# OSWDKPCB.net
KiCad netlist of a schematic drawn in EAGLE
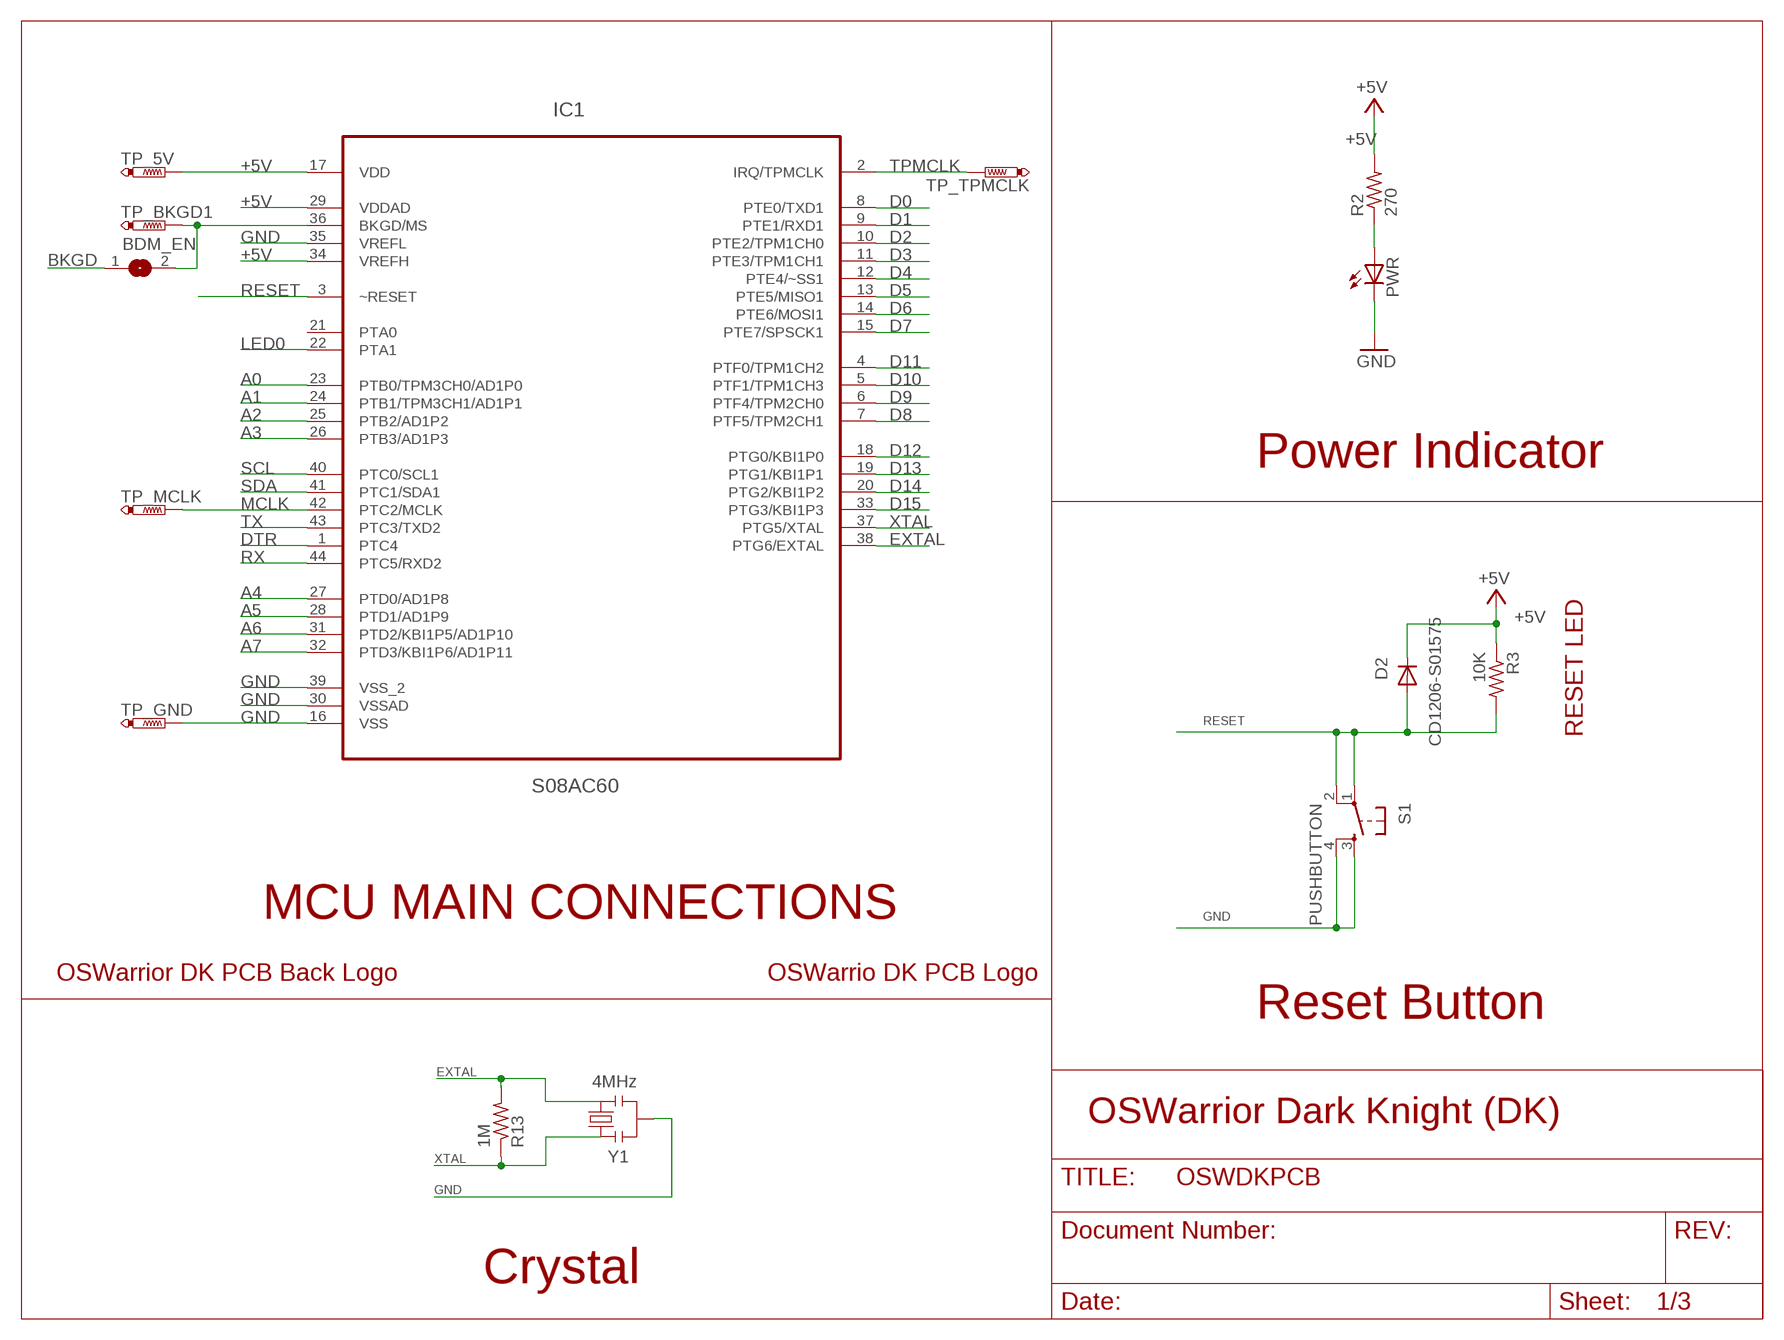
[diagram p0: schematic, sheet 1]
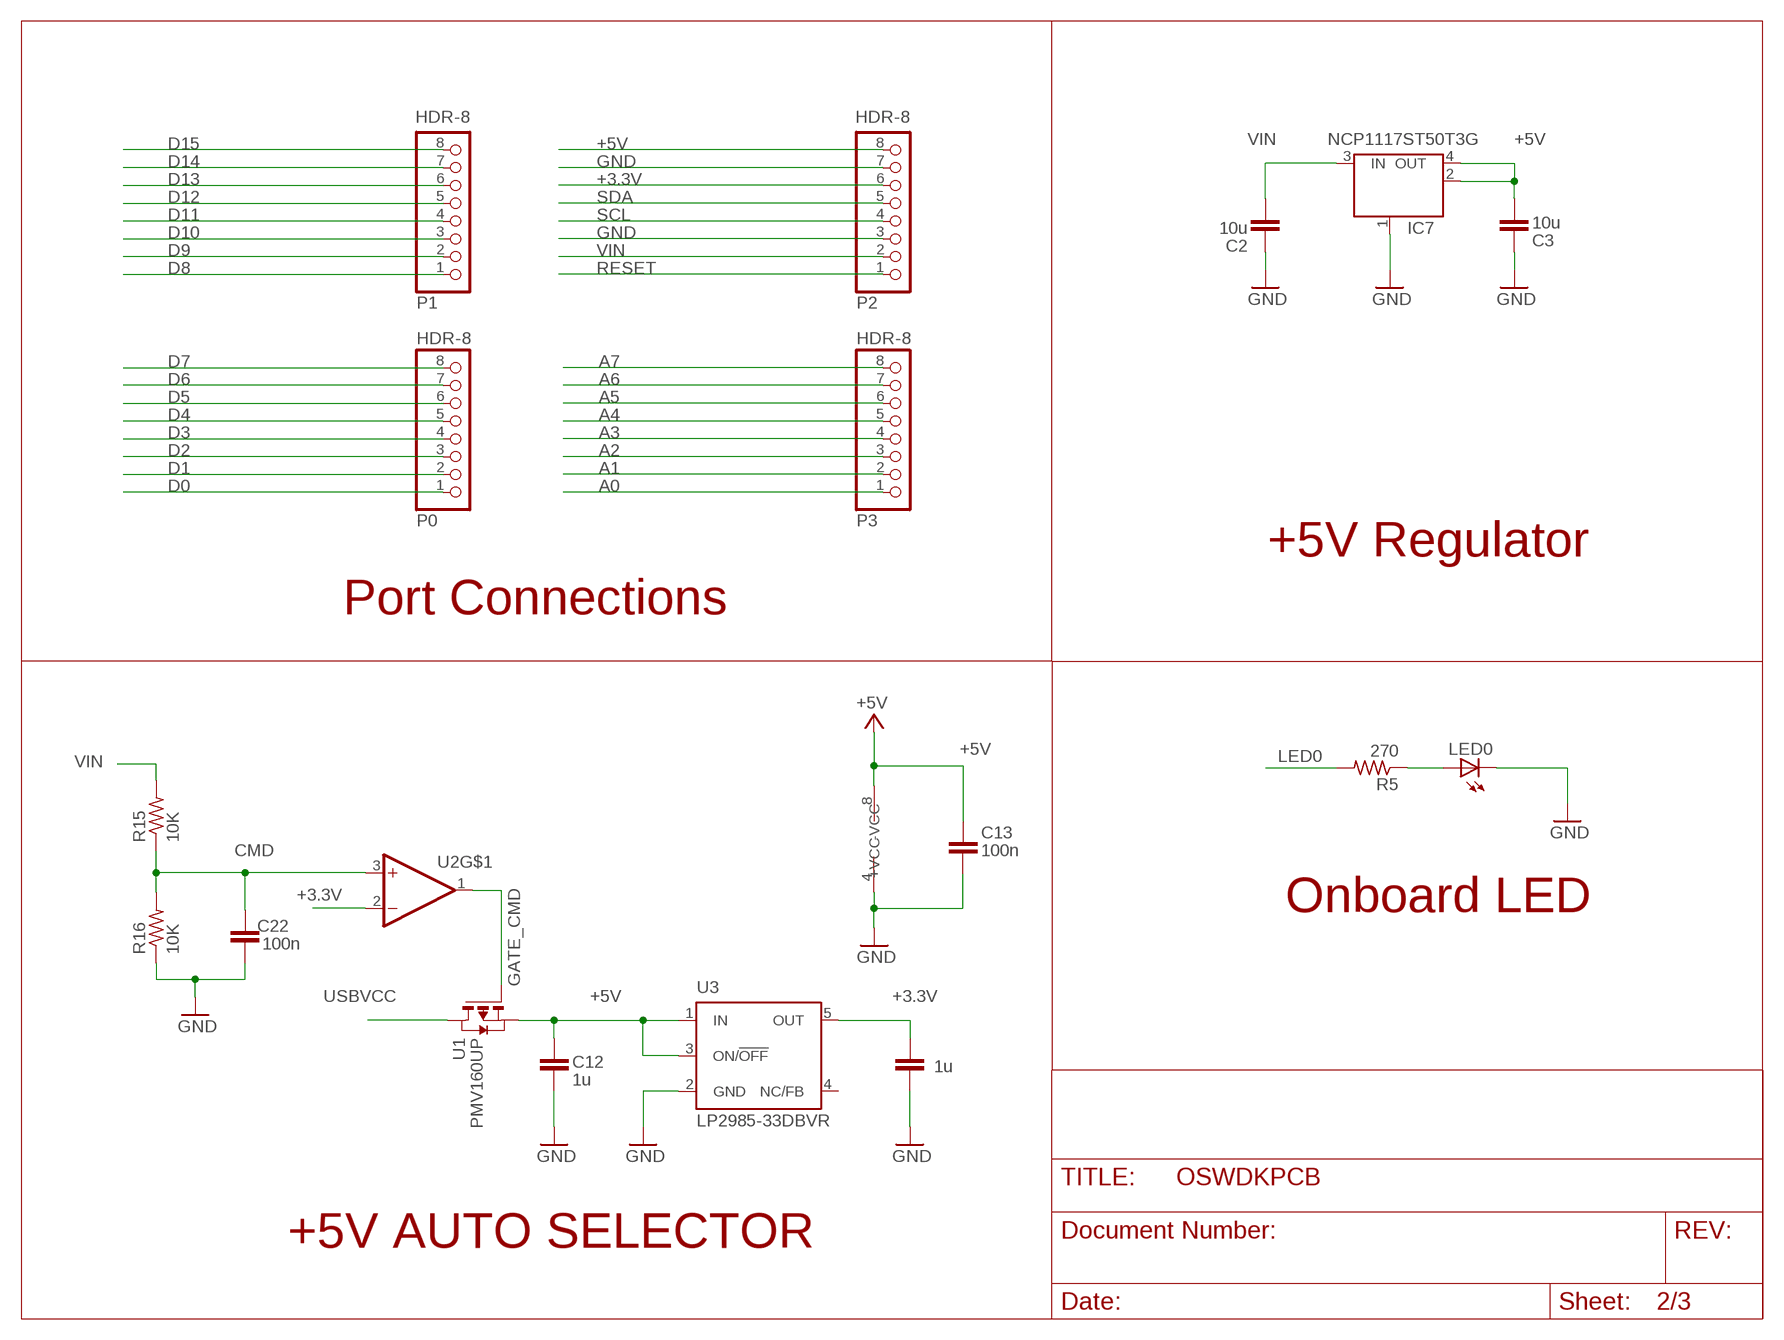
[diagram p1: schematic, sheet 2]
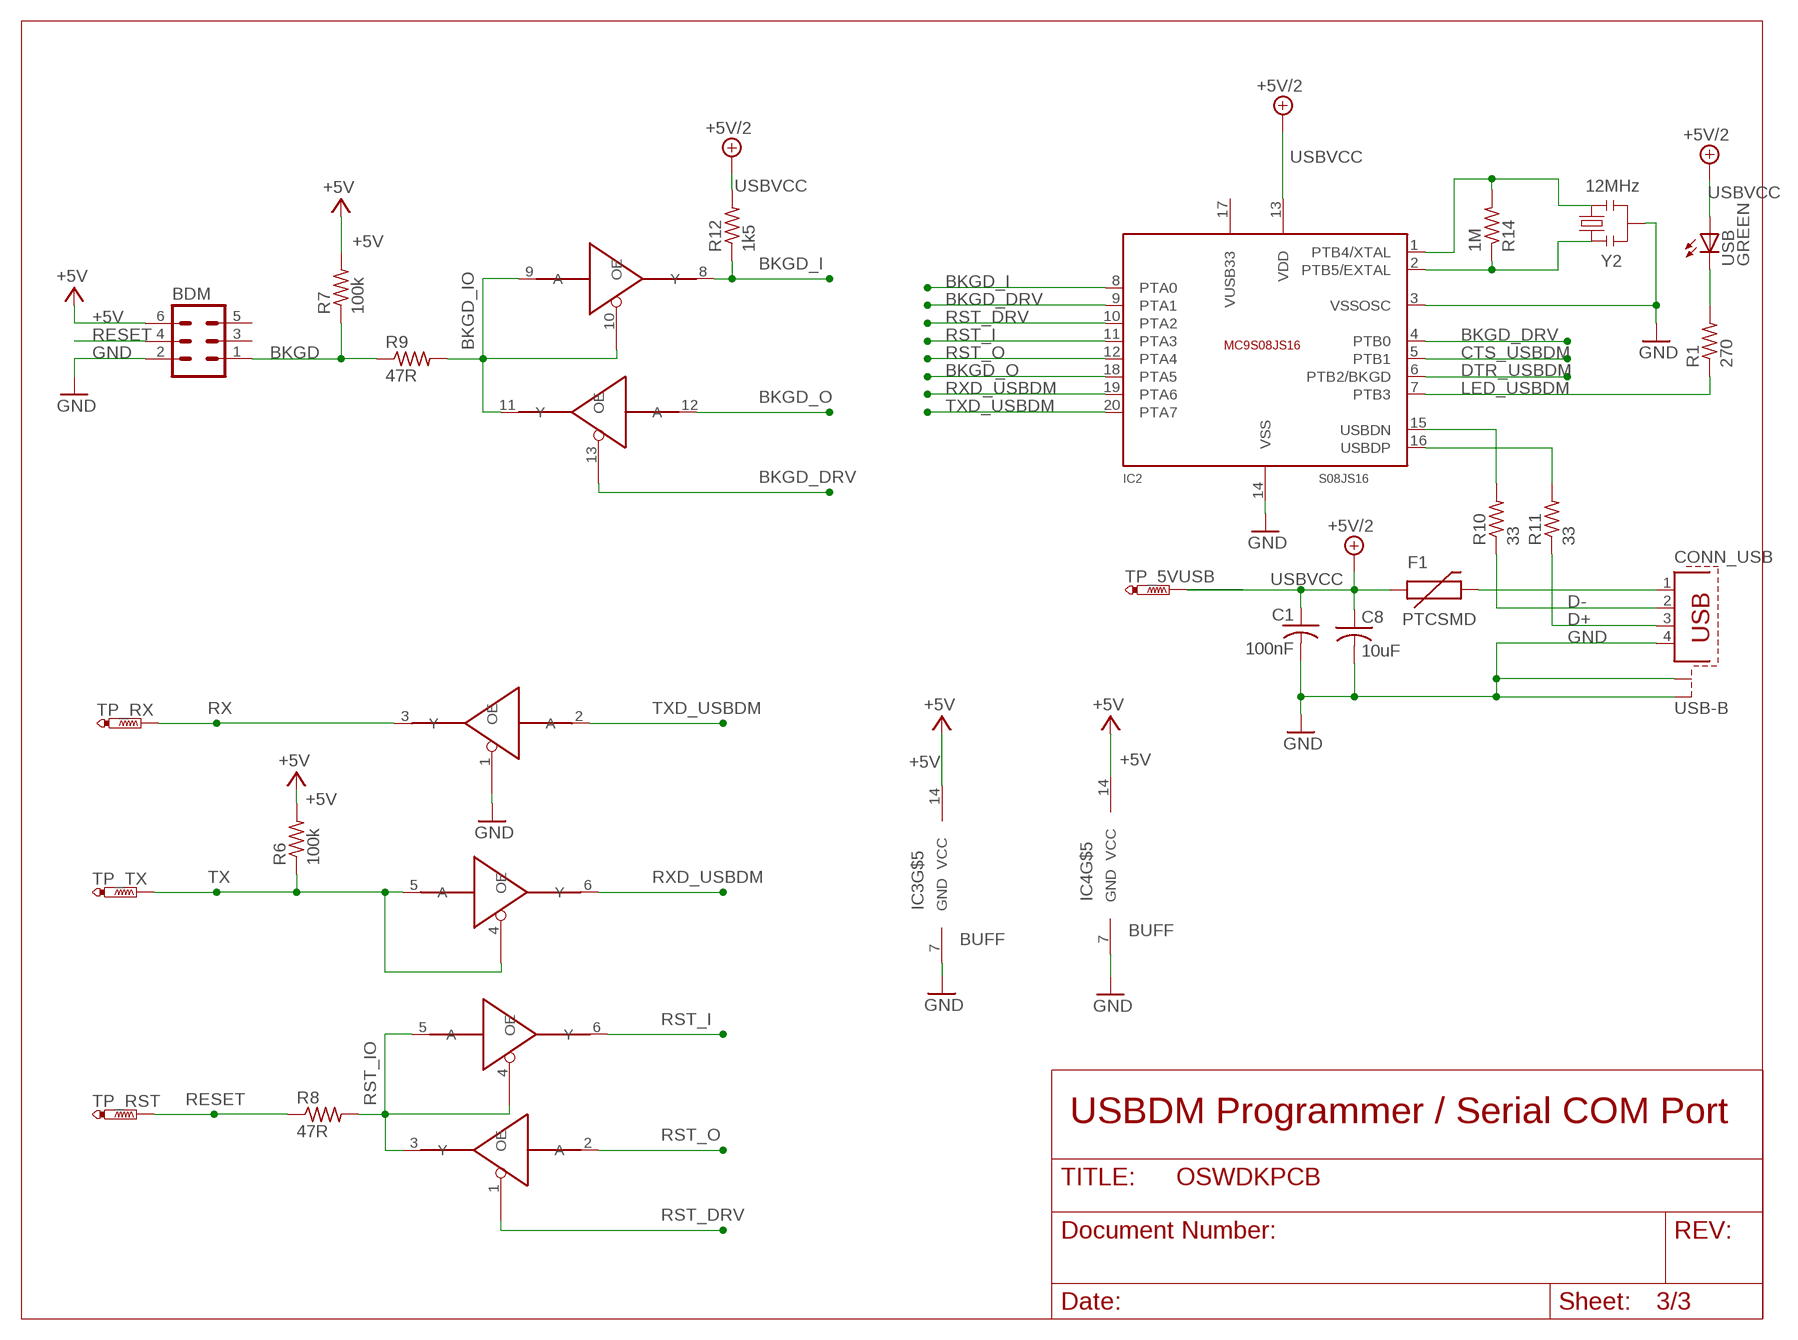
[diagram p2: schematic, sheet 3]

(export (version "E")
  (design (tool "Eeschema 10.0.6"))
  (components
    (comp (ref "BDM_EN")
      (value "SJ")
      (footprint "eagle-import:SJ")
      (libsource (lib "eagle-import") (part "SJ"))
    )
    (comp (ref "D2")
      (value "CD1206-S01575")
      (footprint "eagle-import:SOD123")
      (libsource (lib "eagle-import") (part "DIODE-SOD123"))
    )
    (comp (ref "IC1")
      (value "S08AC60")
      (footprint "eagle-import:LQFP-44")
      (libsource (lib "eagle-import") (part "MC9S08AC48CFGE_LQFP-44"))
    )
    (comp (ref "PWR")
      (value "LEDCHIPLED_0805")
      (footprint "eagle-import:CHIPLED_0805")
      (libsource (lib "eagle-import") (part "LEDCHIPLED_0805"))
    )
    (comp (ref "R2")
      (value "270")
      (footprint "eagle-import:M0805")
      (libsource (lib "eagle-import") (part "R-US_M0805"))
    )
    (comp (ref "R3")
      (value "10K")
      (footprint "eagle-import:M0805")
      (libsource (lib "eagle-import") (part "R-US_M0805"))
    )
    (comp (ref "R13")
      (value "1M")
      (footprint "eagle-import:M0805")
      (libsource (lib "eagle-import") (part "R-US_M0805"))
    )
    (comp (ref "S1")
      (value "PUSHBUTTON")
      (footprint "eagle-import:TACTILE-PTH")
      (libsource (lib "eagle-import") (part "TAC_SWITCHPTH"))
    )
    (comp (ref "TP_5V")
      (value "PTR1B1,27")
      (footprint "eagle-import:B1,27")
      (libsource (lib "eagle-import") (part "PTR1B1,27"))
    )
    (comp (ref "TP_BKGD1")
      (value "PTR1B1,27")
      (footprint "eagle-import:B1,27")
      (libsource (lib "eagle-import") (part "PTR1B1,27"))
    )
    (comp (ref "TP_GND")
      (value "PTR1B1,27")
      (footprint "eagle-import:B1,27")
      (libsource (lib "eagle-import") (part "PTR1B1,27"))
    )
    (comp (ref "TP_MCLK")
      (value "PTR1B1,27")
      (footprint "eagle-import:B1,27")
      (libsource (lib "eagle-import") (part "PTR1B1,27"))
    )
    (comp (ref "TP_TPMCLK")
      (value "PTR1B1,27")
      (footprint "eagle-import:B1,27")
      (libsource (lib "eagle-import") (part "PTR1B1,27"))
    )
    (comp (ref "U$1")
      (value "OSWDK_LOGO")
      (footprint "eagle-import:OSWDK_LOGO")
      (libsource (lib "eagle-import") (part "OSWDK_LOGO"))
    )
    (comp (ref "U$2")
      (value "OSWDK_BACK_LOGO")
      (footprint "eagle-import:OSWDK_BACK_LOGO")
      (libsource (lib "eagle-import") (part "OSWDK_BACK_LOGO"))
    )
    (comp (ref "Y1")
      (value "4MHz")
      (footprint "eagle-import:RESONATOR-SMD")
      (libsource (lib "eagle-import") (part "RESONATORSMD"))
    )
    (comp (ref "BDM")
      (value "MA03-2")
      (footprint "eagle-import:MA03-2")
      (libsource (lib "eagle-import") (part "MA03-2"))
    )
    (comp (ref "C1")
      (value "100nF")
      (footprint "eagle-import:C0805")
      (libsource (lib "eagle-import") (part "C-USC0805"))
    )
    (comp (ref "C8")
      (value "10uF")
      (footprint "eagle-import:C0805")
      (libsource (lib "eagle-import") (part "C-USC0805"))
    )
    (comp (ref "CONN_USB")
      (value "USB-B")
      (footprint "eagle-import:PN61729-S")
      (libsource (lib "eagle-import") (part "PN61729-S"))
    )
    (comp (ref "F1")
      (value "PTCSMD")
      (footprint "eagle-import:PTC-1206")
      (libsource (lib "eagle-import") (part "PTCSMD"))
    )
    (comp (ref "IC2")
      (value "S08JS16")
      (footprint "eagle-import:SOIC-20")
      (libsource (lib "eagle-import") (part "MC9S08JS16CWJ_SOIC-20"))
    )
    (comp (ref "IC3")
      (value "BUFF")
      (footprint "eagle-import:TSSOP-14")
      (libsource (lib "eagle-import") (part "SN74LV125APW_TSSOP-14"))
    )
    (comp (ref "IC4")
      (value "BUFF")
      (footprint "eagle-import:TSSOP-14")
      (libsource (lib "eagle-import") (part "SN74LV125APW_TSSOP-14"))
    )
    (comp (ref "R1")
      (value "270")
      (footprint "eagle-import:M0805")
      (libsource (lib "eagle-import") (part "R-US_M0805"))
    )
    (comp (ref "R6")
      (value "100k")
      (footprint "eagle-import:M0805")
      (libsource (lib "eagle-import") (part "R-US_M0805"))
    )
    (comp (ref "R7")
      (value "100k")
      (footprint "eagle-import:M0805")
      (libsource (lib "eagle-import") (part "R-US_M0805"))
    )
    (comp (ref "R8")
      (value "47R")
      (footprint "eagle-import:M0805")
      (libsource (lib "eagle-import") (part "R-US_M0805"))
    )
    (comp (ref "R9")
      (value "47R")
      (footprint "eagle-import:M0805")
      (libsource (lib "eagle-import") (part "R-US_M0805"))
    )
    (comp (ref "R10")
      (value "33")
      (footprint "eagle-import:M0805")
      (libsource (lib "eagle-import") (part "R-US_M0805"))
    )
    (comp (ref "R11")
      (value "33")
      (footprint "eagle-import:M0805")
      (libsource (lib "eagle-import") (part "R-US_M0805"))
    )
    (comp (ref "R12")
      (value "1k5")
      (footprint "eagle-import:M0805")
      (libsource (lib "eagle-import") (part "R-US_M0805"))
    )
    (comp (ref "R14")
      (value "1M")
      (footprint "eagle-import:M0805")
      (libsource (lib "eagle-import") (part "R-US_M0805"))
    )
    (comp (ref "TP_5VUSB")
      (value "PTR1B1,27")
      (footprint "eagle-import:B1,27")
      (libsource (lib "eagle-import") (part "PTR1B1,27"))
    )
    (comp (ref "TP_RST")
      (value "PTR1B1,27")
      (footprint "eagle-import:B1,27")
      (libsource (lib "eagle-import") (part "PTR1B1,27"))
    )
    (comp (ref "TP_RX")
      (value "PTR1B1,27")
      (footprint "eagle-import:B1,27")
      (libsource (lib "eagle-import") (part "PTR1B1,27"))
    )
    (comp (ref "TP_TX")
      (value "PTR1B1,27")
      (footprint "eagle-import:B1,27")
      (libsource (lib "eagle-import") (part "PTR1B1,27"))
    )
    (comp (ref "USB")
      (value "GREEN")
      (footprint "eagle-import:CHIPLED_0805")
      (libsource (lib "eagle-import") (part "LEDCHIPLED_0805"))
    )
    (comp (ref "Y2")
      (value "12MHz")
      (footprint "eagle-import:RESONATOR-SMD")
      (libsource (lib "eagle-import") (part "RESONATORSMD"))
    )
    (comp (ref "C2")
      (value "10u")
      (footprint "eagle-import:C0805")
      (libsource (lib "eagle-import") (part "C-EUC0805"))
    )
    (comp (ref "C3")
      (value "10u")
      (footprint "eagle-import:C0805")
      (libsource (lib "eagle-import") (part "C-EUC0805"))
    )
    (comp (ref "C12")
      (value "1u")
      (footprint "eagle-import:C0805")
      (libsource (lib "eagle-import") (part "C-EUC0805"))
    )
    (comp (ref "C13")
      (value "100n")
      (footprint "eagle-import:C0805")
      (libsource (lib "eagle-import") (part "C-EUC0805"))
    )
    (comp (ref "C14")
      (value "1u")
      (footprint "eagle-import:C0805")
      (libsource (lib "eagle-import") (part "C-EUC0805"))
    )
    (comp (ref "C22")
      (value "100n")
      (footprint "eagle-import:C0805")
      (libsource (lib "eagle-import") (part "C-EUC0805"))
    )
    (comp (ref "IC7")
      (value "NCP1117ST50T3G")
      (footprint "eagle-import:SOT223")
      (libsource (lib "eagle-import") (part "MC33269ST-3.3T3"))
    )
    (comp (ref "LED0")
      (value "LEDCHIPLED_0805")
      (footprint "eagle-import:CHIPLED_0805")
      (libsource (lib "eagle-import") (part "LEDCHIPLED_0805"))
    )
    (comp (ref "P0")
      (value "HDR-8")
      (footprint "eagle-import:1X08")
      (libsource (lib "eagle-import") (part "PINHD-1X8"))
    )
    (comp (ref "P1")
      (value "HDR-8")
      (footprint "eagle-import:1X08")
      (libsource (lib "eagle-import") (part "PINHD-1X8"))
    )
    (comp (ref "P2")
      (value "HDR-8")
      (footprint "eagle-import:1X08")
      (libsource (lib "eagle-import") (part "PINHD-1X8"))
    )
    (comp (ref "P3")
      (value "HDR-8")
      (footprint "eagle-import:1X08")
      (libsource (lib "eagle-import") (part "PINHD-1X8"))
    )
    (comp (ref "R5")
      (value "270")
      (footprint "eagle-import:M0805")
      (libsource (lib "eagle-import") (part "R-US_M0805"))
    )
    (comp (ref "R15")
      (value "10K")
      (footprint "eagle-import:M0805")
      (libsource (lib "eagle-import") (part "R-US_M0805"))
    )
    (comp (ref "R16")
      (value "10K")
      (footprint "eagle-import:M0805")
      (libsource (lib "eagle-import") (part "R-US_M0805"))
    )
    (comp (ref "U1")
      (value "PMV160UP")
      (footprint "eagle-import:SOT-23")
      (libsource (lib "eagle-import") (part "PMV160UP"))
    )
    (comp (ref "U2")
      (value "RC4558")
      (footprint "eagle-import:SOIC-8")
      (libsource (lib "eagle-import") (part "RC4558"))
    )
    (comp (ref "U3")
      (value "LP2985-33DBVR")
      (footprint "eagle-import:SOT23-DBV")
      (libsource (lib "eagle-import") (part "LP2985-XXDBVR33"))
    )
  )
  (nets
    (net (code "1") (name "+3.3V") (class "Default")
      (node (ref "C14") (pin "2") (pinfunction "2_2") (pintype "passive"))
      (node (ref "P2") (pin "6") (pinfunction "6_6") (pintype "passive"))
      (node (ref "U2") (pin "2") (pinfunction "-IN1_2") (pintype "input"))
      (node (ref "U3") (pin "5") (pinfunction "OUT_5") (pintype "passive"))
    )
    (net (code "2") (name "+5V") (class "Default")
      (node (ref "BDM") (pin "6") (pinfunction "6_6") (pintype "passive"))
      (node (ref "C12") (pin "2") (pinfunction "2_2") (pintype "passive"))
      (node (ref "C13") (pin "1") (pinfunction "1_1") (pintype "passive"))
      (node (ref "C3") (pin "1") (pinfunction "1_1") (pintype "passive"))
      (node (ref "D2") (pin "C") (pinfunction "C_C") (pintype "passive"))
      (node (ref "IC1") (pin "17") (pinfunction "VDD_17") (pintype "power_in"))
      (node (ref "IC1") (pin "29") (pinfunction "VDDAD_29") (pintype "power_in"))
      (node (ref "IC1") (pin "34") (pinfunction "VREFH_34") (pintype "input"))
      (node (ref "IC3") (pin "14") (pinfunction "VCC_14") (pintype "power_in"))
      (node (ref "IC4") (pin "14") (pinfunction "VCC_14") (pintype "power_in"))
      (node (ref "IC7") (pin "2") (pinfunction "OUT_2") (pintype "passive"))
      (node (ref "IC7") (pin "4") (pinfunction "OUT_4") (pintype "passive"))
      (node (ref "P2") (pin "8") (pinfunction "8_8") (pintype "passive"))
      (node (ref "R2") (pin "2") (pinfunction "2_2") (pintype "passive"))
      (node (ref "R3") (pin "1") (pinfunction "1_1") (pintype "passive"))
      (node (ref "R6") (pin "2") (pinfunction "2_2") (pintype "passive"))
      (node (ref "R7") (pin "2") (pinfunction "2_2") (pintype "passive"))
      (node (ref "TP_5V") (pin "TP") (pinfunction "TP_TP") (pintype "input"))
      (node (ref "U1") (pin "2") (pinfunction "S_2") (pintype "passive"))
      (node (ref "U2") (pin "8") (pinfunction "+VCC_8") (pintype "power_in"))
      (node (ref "U3") (pin "1") (pinfunction "IN_1") (pintype "input"))
      (node (ref "U3") (pin "3") (pinfunction "ON/~{OFF}_3") (pintype "input"))
    )
    (net (code "3") (name "A0") (class "Default")
      (node (ref "IC1") (pin "23") (pinfunction "PTB0/TPM3CH0/AD1P0_23") (pintype "bidirectional"))
      (node (ref "P3") (pin "1") (pinfunction "1_1") (pintype "passive"))
    )
    (net (code "4") (name "A1") (class "Default")
      (node (ref "IC1") (pin "24") (pinfunction "PTB1/TPM3CH1/AD1P1_24") (pintype "bidirectional"))
      (node (ref "P3") (pin "2") (pinfunction "2_2") (pintype "passive"))
    )
    (net (code "5") (name "A2") (class "Default")
      (node (ref "IC1") (pin "25") (pinfunction "PTB2/AD1P2_25") (pintype "bidirectional"))
      (node (ref "P3") (pin "3") (pinfunction "3_3") (pintype "passive"))
    )
    (net (code "6") (name "A3") (class "Default")
      (node (ref "IC1") (pin "26") (pinfunction "PTB3/AD1P3_26") (pintype "bidirectional"))
      (node (ref "P3") (pin "4") (pinfunction "4_4") (pintype "passive"))
    )
    (net (code "7") (name "A4") (class "Default")
      (node (ref "IC1") (pin "27") (pinfunction "PTD0/AD1P8_27") (pintype "bidirectional"))
      (node (ref "P3") (pin "5") (pinfunction "5_5") (pintype "passive"))
    )
    (net (code "8") (name "A5") (class "Default")
      (node (ref "IC1") (pin "28") (pinfunction "PTD1/AD1P9_28") (pintype "bidirectional"))
      (node (ref "P3") (pin "6") (pinfunction "6_6") (pintype "passive"))
    )
    (net (code "9") (name "A6") (class "Default")
      (node (ref "IC1") (pin "31") (pinfunction "PTD2/KBI1P5/AD1P10_31") (pintype "bidirectional"))
      (node (ref "P3") (pin "7") (pinfunction "7_7") (pintype "passive"))
    )
    (net (code "10") (name "A7") (class "Default")
      (node (ref "IC1") (pin "32") (pinfunction "PTD3/KBI1P6/AD1P11_32") (pintype "bidirectional"))
      (node (ref "P3") (pin "8") (pinfunction "8_8") (pintype "passive"))
    )
    (net (code "11") (name "BKGD") (class "Default")
      (node (ref "BDM") (pin "1") (pinfunction "1_1") (pintype "passive"))
      (node (ref "BDM_EN") (pin "1") (pinfunction "1_1") (pintype "passive"))
      (node (ref "R7") (pin "1") (pinfunction "1_1") (pintype "passive"))
      (node (ref "R9") (pin "1") (pinfunction "1_1") (pintype "passive"))
    )
    (net (code "12") (name "BKGD_DRV") (class "Default")
      (node (ref "IC2") (pin "4") (pinfunction "PTB0_4") (pintype "bidirectional"))
      (node (ref "IC2") (pin "9") (pinfunction "PTA1_9") (pintype "bidirectional"))
      (node (ref "IC4") (pin "13") (pinfunction "OE_13") (pintype "input"))
    )
    (net (code "13") (name "BKGD_I") (class "Default")
      (node (ref "IC2") (pin "8") (pinfunction "PTA0_8") (pintype "bidirectional"))
      (node (ref "IC4") (pin "8") (pinfunction "Y_8") (pintype "output"))
      (node (ref "R12") (pin "1") (pinfunction "1_1") (pintype "passive"))
    )
    (net (code "14") (name "BKGD_IO") (class "Default")
      (node (ref "IC4") (pin "10") (pinfunction "OE_10") (pintype "input"))
      (node (ref "IC4") (pin "11") (pinfunction "Y_11") (pintype "output"))
      (node (ref "IC4") (pin "9") (pinfunction "A_9") (pintype "input"))
      (node (ref "R9") (pin "2") (pinfunction "2_2") (pintype "passive"))
    )
    (net (code "15") (name "BKGD_O") (class "Default")
      (node (ref "IC2") (pin "18") (pinfunction "PTA5_18") (pintype "bidirectional"))
      (node (ref "IC4") (pin "12") (pinfunction "A_12") (pintype "input"))
    )
    (net (code "16") (name "CMD") (class "Default")
      (node (ref "C22") (pin "2") (pinfunction "2_2") (pintype "passive"))
      (node (ref "R15") (pin "1") (pinfunction "1_1") (pintype "passive"))
      (node (ref "R16") (pin "2") (pinfunction "2_2") (pintype "passive"))
      (node (ref "U2") (pin "3") (pinfunction "+IN1_3") (pintype "input"))
    )
    (net (code "17") (name "CTS_USBDM") (class "Default")
      (node (ref "IC2") (pin "5") (pinfunction "PTB1_5") (pintype "bidirectional"))
    )
    (net (code "18") (name "D+") (class "Default")
      (node (ref "CONN_USB") (pin "3") (pinfunction "3_3") (pintype "passive"))
      (node (ref "R11") (pin "1") (pinfunction "1_1") (pintype "passive"))
    )
    (net (code "19") (name "D-") (class "Default")
      (node (ref "CONN_USB") (pin "2") (pinfunction "2_2") (pintype "passive"))
      (node (ref "R10") (pin "1") (pinfunction "1_1") (pintype "passive"))
    )
    (net (code "20") (name "D0") (class "Default")
      (node (ref "IC1") (pin "8") (pinfunction "PTE0/TXD1_8") (pintype "bidirectional"))
      (node (ref "P0") (pin "1") (pinfunction "1_1") (pintype "passive"))
    )
    (net (code "21") (name "D1") (class "Default")
      (node (ref "IC1") (pin "9") (pinfunction "PTE1/RXD1_9") (pintype "bidirectional"))
      (node (ref "P0") (pin "2") (pinfunction "2_2") (pintype "passive"))
    )
    (net (code "22") (name "D2") (class "Default")
      (node (ref "IC1") (pin "10") (pinfunction "PTE2/TPM1CH0_10") (pintype "bidirectional"))
      (node (ref "P0") (pin "3") (pinfunction "3_3") (pintype "passive"))
    )
    (net (code "23") (name "D3") (class "Default")
      (node (ref "IC1") (pin "11") (pinfunction "PTE3/TPM1CH1_11") (pintype "bidirectional"))
      (node (ref "P0") (pin "4") (pinfunction "4_4") (pintype "passive"))
    )
    (net (code "24") (name "D4") (class "Default")
      (node (ref "IC1") (pin "12") (pinfunction "PTE4/~{SS1}_12") (pintype "bidirectional"))
      (node (ref "P0") (pin "5") (pinfunction "5_5") (pintype "passive"))
    )
    (net (code "25") (name "D5") (class "Default")
      (node (ref "IC1") (pin "13") (pinfunction "PTE5/MISO1_13") (pintype "bidirectional"))
      (node (ref "P0") (pin "6") (pinfunction "6_6") (pintype "passive"))
    )
    (net (code "26") (name "D6") (class "Default")
      (node (ref "IC1") (pin "14") (pinfunction "PTE6/MOSI1_14") (pintype "bidirectional"))
      (node (ref "P0") (pin "7") (pinfunction "7_7") (pintype "passive"))
    )
    (net (code "27") (name "D7") (class "Default")
      (node (ref "IC1") (pin "15") (pinfunction "PTE7/SPSCK1_15") (pintype "bidirectional"))
      (node (ref "P0") (pin "8") (pinfunction "8_8") (pintype "passive"))
    )
    (net (code "28") (name "D8") (class "Default")
      (node (ref "IC1") (pin "7") (pinfunction "PTF5/TPM2CH1_7") (pintype "bidirectional"))
      (node (ref "P1") (pin "1") (pinfunction "1_1") (pintype "passive"))
    )
    (net (code "29") (name "D9") (class "Default")
      (node (ref "IC1") (pin "6") (pinfunction "PTF4/TPM2CH0_6") (pintype "bidirectional"))
      (node (ref "P1") (pin "2") (pinfunction "2_2") (pintype "passive"))
    )
    (net (code "30") (name "D10") (class "Default")
      (node (ref "IC1") (pin "5") (pinfunction "PTF1/TPM1CH3_5") (pintype "bidirectional"))
      (node (ref "P1") (pin "3") (pinfunction "3_3") (pintype "passive"))
    )
    (net (code "31") (name "D11") (class "Default")
      (node (ref "IC1") (pin "4") (pinfunction "PTF0/TPM1CH2_4") (pintype "bidirectional"))
      (node (ref "P1") (pin "4") (pinfunction "4_4") (pintype "passive"))
    )
    (net (code "32") (name "D12") (class "Default")
      (node (ref "IC1") (pin "18") (pinfunction "PTG0/KBI1P0_18") (pintype "bidirectional"))
      (node (ref "P1") (pin "5") (pinfunction "5_5") (pintype "passive"))
    )
    (net (code "33") (name "D13") (class "Default")
      (node (ref "IC1") (pin "19") (pinfunction "PTG1/KBI1P1_19") (pintype "bidirectional"))
      (node (ref "P1") (pin "6") (pinfunction "6_6") (pintype "passive"))
    )
    (net (code "34") (name "D14") (class "Default")
      (node (ref "IC1") (pin "20") (pinfunction "PTG2/KBI1P2_20") (pintype "bidirectional"))
      (node (ref "P1") (pin "7") (pinfunction "7_7") (pintype "passive"))
    )
    (net (code "35") (name "D15") (class "Default")
      (node (ref "IC1") (pin "33") (pinfunction "PTG3/KBI1P3_33") (pintype "bidirectional"))
      (node (ref "P1") (pin "8") (pinfunction "8_8") (pintype "passive"))
    )
    (net (code "36") (name "DTR") (class "Default")
      (node (ref "IC1") (pin "1") (pinfunction "PTC4_1") (pintype "bidirectional"))
    )
    (net (code "37") (name "DTR_USBDM") (class "Default")
      (node (ref "IC2") (pin "6") (pinfunction "PTB2/BKGD_6") (pintype "bidirectional"))
    )
    (net (code "38") (name "EXTAL") (class "Default")
      (node (ref "IC1") (pin "38") (pinfunction "PTG6/EXTAL_38") (pintype "bidirectional"))
      (node (ref "R13") (pin "2") (pinfunction "2_2") (pintype "passive"))
      (node (ref "Y1") (pin "3") (pinfunction "3_3") (pintype "passive"))
    )
    (net (code "39") (name "GATE_CMD") (class "Default")
      (node (ref "U1") (pin "3") (pinfunction "G_3") (pintype "passive"))
      (node (ref "U2") (pin "1") (pinfunction "OUT1_1") (pintype "output"))
    )
    (net (code "40") (name "GND") (class "Default")
      (node (ref "BDM") (pin "2") (pinfunction "2_2") (pintype "passive"))
      (node (ref "C1") (pin "2") (pinfunction "2_2") (pintype "passive"))
      (node (ref "C12") (pin "1") (pinfunction "1_1") (pintype "passive"))
      (node (ref "C13") (pin "2") (pinfunction "2_2") (pintype "passive"))
      (node (ref "C14") (pin "1") (pinfunction "1_1") (pintype "passive"))
      (node (ref "C2") (pin "2") (pinfunction "2_2") (pintype "passive"))
      (node (ref "C22") (pin "1") (pinfunction "1_1") (pintype "passive"))
      (node (ref "C3") (pin "2") (pinfunction "2_2") (pintype "passive"))
      (node (ref "C8") (pin "2") (pinfunction "2_2") (pintype "passive"))
      (node (ref "CONN_USB") (pin "4") (pinfunction "4_4") (pintype "passive"))
      (node (ref "CONN_USB") (pin "S1") (pinfunction "S1_S1") (pintype "passive"))
      (node (ref "CONN_USB") (pin "S2") (pinfunction "S2_S2") (pintype "passive"))
      (node (ref "IC1") (pin "16") (pinfunction "VSS_16") (pintype "power_in"))
      (node (ref "IC1") (pin "30") (pinfunction "VSSAD_30") (pintype "power_in"))
      (node (ref "IC1") (pin "35") (pinfunction "VREFL_35") (pintype "input"))
      (node (ref "IC1") (pin "39") (pinfunction "VSS_2_39") (pintype "power_in"))
      (node (ref "IC2") (pin "14") (pinfunction "VSS_14") (pintype "power_in"))
      (node (ref "IC2") (pin "3") (pinfunction "VSSOSC_3") (pintype "power_in"))
      (node (ref "IC3") (pin "1") (pinfunction "OE_1") (pintype "input"))
      (node (ref "IC3") (pin "7") (pinfunction "GND_7") (pintype "power_in"))
      (node (ref "IC4") (pin "7") (pinfunction "GND_7") (pintype "power_in"))
      (node (ref "IC7") (pin "1") (pinfunction "GND/ADJ_1") (pintype "input"))
      (node (ref "LED0") (pin "C") (pinfunction "C_C") (pintype "passive"))
      (node (ref "P2") (pin "3") (pinfunction "3_3") (pintype "passive"))
      (node (ref "P2") (pin "7") (pinfunction "7_7") (pintype "passive"))
      (node (ref "PWR") (pin "C") (pinfunction "C_C") (pintype "passive"))
      (node (ref "R16") (pin "1") (pinfunction "1_1") (pintype "passive"))
      (node (ref "S1") (pin "3") (pinfunction "3_3") (pintype "passive"))
      (node (ref "S1") (pin "4") (pinfunction "4_4") (pintype "passive"))
      (node (ref "TP_GND") (pin "TP") (pinfunction "TP_TP") (pintype "input"))
      (node (ref "U2") (pin "4") (pinfunction "-VCC_4") (pintype "power_in"))
      (node (ref "U3") (pin "2") (pinfunction "GND_2") (pintype "power_in"))
      (node (ref "Y1") (pin "2") (pinfunction "2_2") (pintype "passive"))
      (node (ref "Y2") (pin "2") (pinfunction "2_2") (pintype "passive"))
    )
    (net (code "41") (name "LED0") (class "Default")
      (node (ref "IC1") (pin "22") (pinfunction "PTA1_22") (pintype "bidirectional"))
      (node (ref "R5") (pin "2") (pinfunction "2_2") (pintype "passive"))
    )
    (net (code "42") (name "LED_USBDM") (class "Default")
      (node (ref "IC2") (pin "7") (pinfunction "PTB3_7") (pintype "bidirectional"))
      (node (ref "R1") (pin "1") (pinfunction "1_1") (pintype "passive"))
    )
    (net (code "43") (name "MCLK") (class "Default")
      (node (ref "IC1") (pin "42") (pinfunction "PTC2/MCLK_42") (pintype "bidirectional"))
      (node (ref "TP_MCLK") (pin "TP") (pinfunction "TP_TP") (pintype "input"))
    )
    (net (code "44") (name "Net-(CONN_USB-Pad1)") (class "Default")
      (node (ref "CONN_USB") (pin "1") (pinfunction "1_1") (pintype "passive"))
      (node (ref "F1") (pin "2") (pinfunction "2_2") (pintype "bidirectional"))
    )
    (net (code "45") (name "Net-(IC1-BKGD{slash}MS)") (class "Default")
      (node (ref "BDM_EN") (pin "2") (pinfunction "2_2") (pintype "passive"))
      (node (ref "IC1") (pin "36") (pinfunction "BKGD/MS_36") (pintype "bidirectional"))
      (node (ref "TP_BKGD1") (pin "TP") (pinfunction "TP_TP") (pintype "input"))
    )
    (net (code "46") (name "Net-(IC2-PTB4{slash}XTAL)") (class "Default")
      (node (ref "IC2") (pin "1") (pinfunction "PTB4/XTAL_1") (pintype "bidirectional"))
      (node (ref "R14") (pin "2") (pinfunction "2_2") (pintype "passive"))
      (node (ref "Y2") (pin "3") (pinfunction "3_3") (pintype "passive"))
    )
    (net (code "47") (name "Net-(IC2-PTB5{slash}EXTAL)") (class "Default")
      (node (ref "IC2") (pin "2") (pinfunction "PTB5/EXTAL_2") (pintype "bidirectional"))
      (node (ref "R14") (pin "1") (pinfunction "1_1") (pintype "passive"))
      (node (ref "Y2") (pin "1") (pinfunction "1_1") (pintype "passive"))
    )
    (net (code "48") (name "Net-(IC2-USBDN)") (class "Default")
      (node (ref "IC2") (pin "15") (pinfunction "USBDN_15") (pintype "bidirectional"))
      (node (ref "R10") (pin "2") (pinfunction "2_2") (pintype "passive"))
    )
    (net (code "49") (name "Net-(IC2-USBDP)") (class "Default")
      (node (ref "IC2") (pin "16") (pinfunction "USBDP_16") (pintype "bidirectional"))
      (node (ref "R11") (pin "2") (pinfunction "2_2") (pintype "passive"))
    )
    (net (code "50") (name "Net-(LED0-PadA)") (class "Default")
      (node (ref "LED0") (pin "A") (pinfunction "A_A") (pintype "passive"))
      (node (ref "R5") (pin "1") (pinfunction "1_1") (pintype "passive"))
    )
    (net (code "51") (name "Net-(PWR-PadA)") (class "Default")
      (node (ref "PWR") (pin "A") (pinfunction "A_A") (pintype "passive"))
      (node (ref "R2") (pin "1") (pinfunction "1_1") (pintype "passive"))
    )
    (net (code "52") (name "Net-(R1-Pad2)") (class "Default")
      (node (ref "R1") (pin "2") (pinfunction "2_2") (pintype "passive"))
      (node (ref "USB") (pin "C") (pinfunction "C_C") (pintype "passive"))
    )
    (net (code "53") (name "RESET") (class "Default")
      (node (ref "BDM") (pin "4") (pinfunction "4_4") (pintype "passive"))
      (node (ref "D2") (pin "A") (pinfunction "A_A") (pintype "passive"))
      (node (ref "IC1") (pin "3") (pinfunction "~{RESET}_3") (pintype "input"))
      (node (ref "P2") (pin "1") (pinfunction "1_1") (pintype "passive"))
      (node (ref "R3") (pin "2") (pinfunction "2_2") (pintype "passive"))
      (node (ref "R8") (pin "1") (pinfunction "1_1") (pintype "passive"))
      (node (ref "S1") (pin "1") (pinfunction "1_1") (pintype "passive"))
      (node (ref "S1") (pin "2") (pinfunction "2_2") (pintype "passive"))
      (node (ref "TP_RST") (pin "TP") (pinfunction "TP_TP") (pintype "input"))
    )
    (net (code "54") (name "RST_DRV") (class "Default")
      (node (ref "IC2") (pin "10") (pinfunction "PTA2_10") (pintype "bidirectional"))
      (node (ref "IC4") (pin "1") (pinfunction "OE_1") (pintype "input"))
    )
    (net (code "55") (name "RST_I") (class "Default")
      (node (ref "IC2") (pin "11") (pinfunction "PTA3_11") (pintype "bidirectional"))
      (node (ref "IC4") (pin "6") (pinfunction "Y_6") (pintype "output"))
    )
    (net (code "56") (name "RST_IO") (class "Default")
      (node (ref "IC4") (pin "3") (pinfunction "Y_3") (pintype "output"))
      (node (ref "IC4") (pin "4") (pinfunction "OE_4") (pintype "input"))
      (node (ref "IC4") (pin "5") (pinfunction "A_5") (pintype "input"))
      (node (ref "R8") (pin "2") (pinfunction "2_2") (pintype "passive"))
    )
    (net (code "57") (name "RST_O") (class "Default")
      (node (ref "IC2") (pin "12") (pinfunction "PTA4_12") (pintype "bidirectional"))
      (node (ref "IC4") (pin "2") (pinfunction "A_2") (pintype "input"))
    )
    (net (code "58") (name "RX") (class "Default")
      (node (ref "IC1") (pin "44") (pinfunction "PTC5/RXD2_44") (pintype "bidirectional"))
      (node (ref "IC3") (pin "3") (pinfunction "Y_3") (pintype "output"))
      (node (ref "TP_RX") (pin "TP") (pinfunction "TP_TP") (pintype "input"))
    )
    (net (code "59") (name "RXD_USBDM") (class "Default")
      (node (ref "IC2") (pin "19") (pinfunction "PTA6_19") (pintype "bidirectional"))
      (node (ref "IC3") (pin "6") (pinfunction "Y_6") (pintype "output"))
    )
    (net (code "60") (name "SCL") (class "Default")
      (node (ref "IC1") (pin "40") (pinfunction "PTC0/SCL1_40") (pintype "bidirectional"))
      (node (ref "P2") (pin "4") (pinfunction "4_4") (pintype "passive"))
    )
    (net (code "61") (name "SDA") (class "Default")
      (node (ref "IC1") (pin "41") (pinfunction "PTC1/SDA1_41") (pintype "bidirectional"))
      (node (ref "P2") (pin "5") (pinfunction "5_5") (pintype "passive"))
    )
    (net (code "62") (name "TPMCLK") (class "Default")
      (node (ref "IC1") (pin "2") (pinfunction "IRQ/TPMCLK_2") (pintype "bidirectional"))
      (node (ref "TP_TPMCLK") (pin "TP") (pinfunction "TP_TP") (pintype "input"))
    )
    (net (code "63") (name "TX") (class "Default")
      (node (ref "IC1") (pin "43") (pinfunction "PTC3/TXD2_43") (pintype "bidirectional"))
      (node (ref "IC3") (pin "4") (pinfunction "OE_4") (pintype "input"))
      (node (ref "IC3") (pin "5") (pinfunction "A_5") (pintype "input"))
      (node (ref "R6") (pin "1") (pinfunction "1_1") (pintype "passive"))
      (node (ref "TP_TX") (pin "TP") (pinfunction "TP_TP") (pintype "input"))
    )
    (net (code "64") (name "TXD_USBDM") (class "Default")
      (node (ref "IC2") (pin "20") (pinfunction "PTA7_20") (pintype "bidirectional"))
      (node (ref "IC3") (pin "2") (pinfunction "A_2") (pintype "input"))
    )
    (net (code "65") (name "USBVCC") (class "Default")
      (node (ref "C1") (pin "1") (pinfunction "1_1") (pintype "passive"))
      (node (ref "C8") (pin "1") (pinfunction "1_1") (pintype "passive"))
      (node (ref "F1") (pin "1") (pinfunction "1_1") (pintype "bidirectional"))
      (node (ref "IC2") (pin "13") (pinfunction "VDD_13") (pintype "power_in"))
      (node (ref "R12") (pin "2") (pinfunction "2_2") (pintype "passive"))
      (node (ref "TP_5VUSB") (pin "TP") (pinfunction "TP_TP") (pintype "input"))
      (node (ref "U1") (pin "1") (pinfunction "D_1") (pintype "passive"))
      (node (ref "USB") (pin "A") (pinfunction "A_A") (pintype "passive"))
    )
    (net (code "66") (name "VIN") (class "Default")
      (node (ref "C2") (pin "1") (pinfunction "1_1") (pintype "passive"))
      (node (ref "IC7") (pin "3") (pinfunction "IN_3") (pintype "input"))
      (node (ref "P2") (pin "2") (pinfunction "2_2") (pintype "passive"))
      (node (ref "R15") (pin "2") (pinfunction "2_2") (pintype "passive"))
    )
    (net (code "67") (name "VUSB33") (class "Default")
      (node (ref "IC2") (pin "17") (pinfunction "VUSB33_17") (pintype "power_in"))
    )
    (net (code "68") (name "XTAL") (class "Default")
      (node (ref "IC1") (pin "37") (pinfunction "PTG5/XTAL_37") (pintype "bidirectional"))
      (node (ref "R13") (pin "1") (pinfunction "1_1") (pintype "passive"))
      (node (ref "Y1") (pin "1") (pinfunction "1_1") (pintype "passive"))
    )
    (net (code "69") (name "unconnected-(BDM-Pad3)") (class "Default")
      (node (ref "BDM") (pin "3") (pinfunction "3_3") (pintype "passive"))
    )
    (net (code "70") (name "unconnected-(BDM-Pad5)") (class "Default")
      (node (ref "BDM") (pin "5") (pinfunction "5_5") (pintype "passive"))
    )
    (net (code "71") (name "unconnected-(IC1-PTA0-Pad21)") (class "Default")
      (node (ref "IC1") (pin "21") (pinfunction "PTA0_21") (pintype "bidirectional"))
    )
    (net (code "72") (name "unconnected-(U3-NC{slash}FB-Pad4)") (class "Default")
      (node (ref "U3") (pin "4") (pinfunction "NC/FB_4") (pintype "passive"))
    )
  )
)
